# PartA.net
KiCad netlist of a schematic drawn in Altium Designer
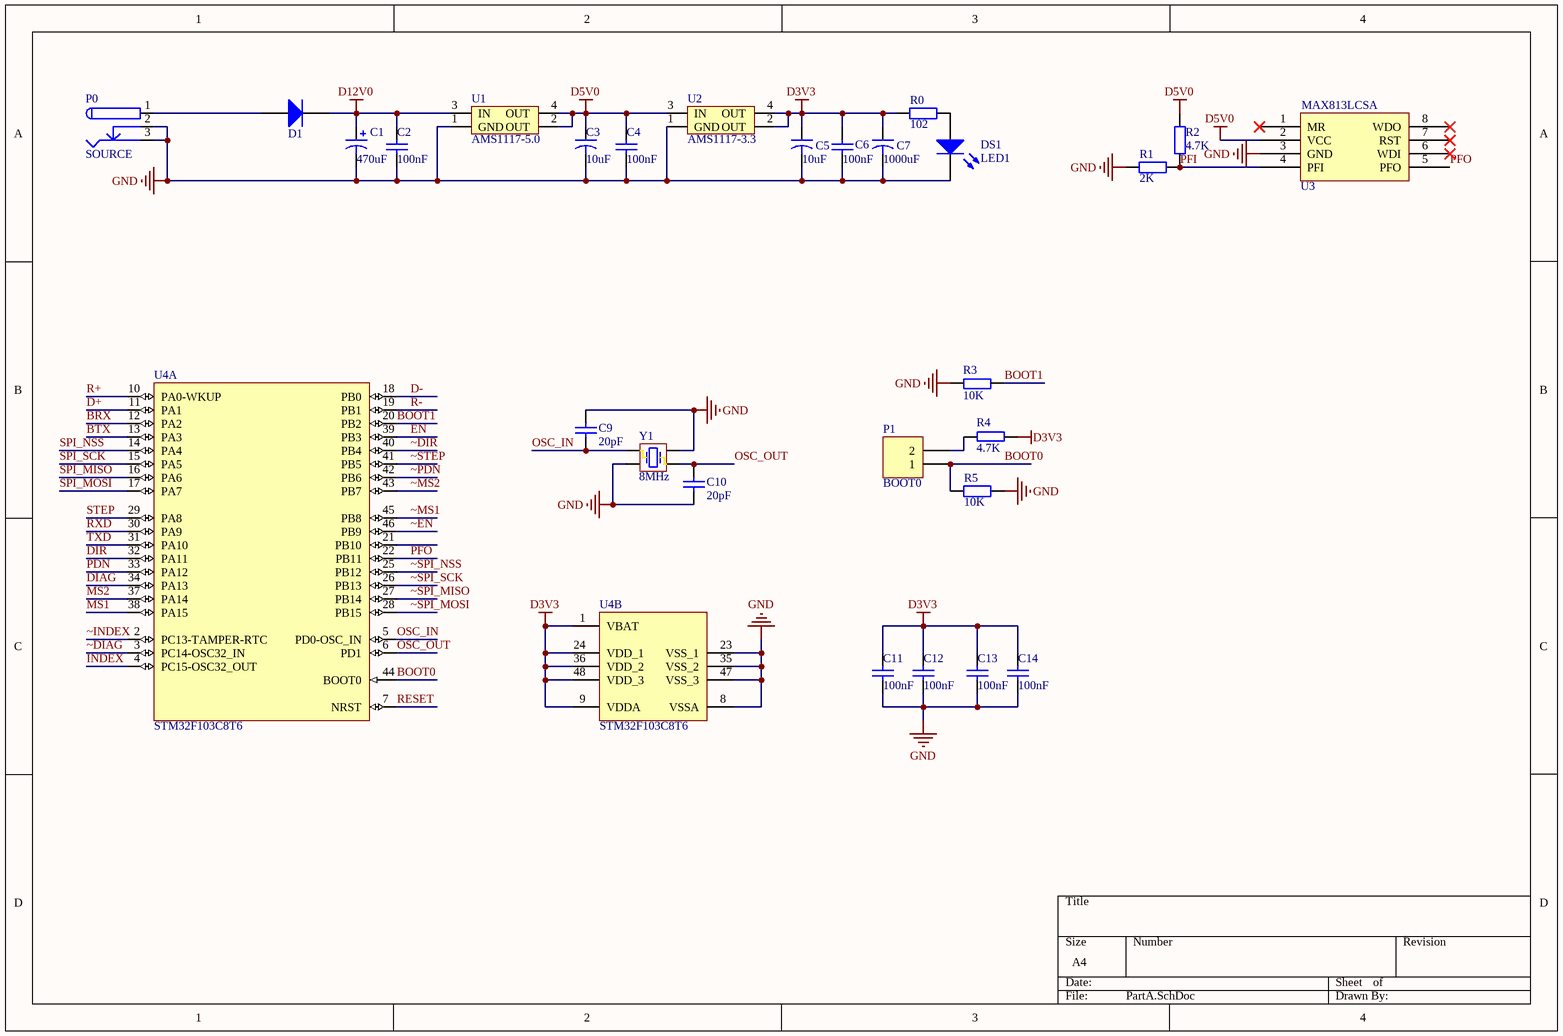
[diagram p0: PartA.SchDoc]

(export (version "E")
  (design (tool "Eeschema 10.0.6"))
  (components
    (comp (ref "C1")
      (value "470uF")
      (footprint "CAP8")
      (description "470UF      16V      CD10X10D5")
      (libsource (lib "平台原理图symbol图库V1.0") (part "C470UF016S"))
    )
    (comp (ref "C2")
      (value "100nF")
      (footprint "0603C")
      (description "Capacitor")
      (fields (field (name "PUBLISHER") "Altium Limited"))
      (libsource (lib "Crazy_PCB") (part "Cap"))
    )
    (comp (ref "C3")
      (value "10uF")
      (footprint "3216")
      (fields (field (name "VAULE") "10uF"))
      (libsource (lib "Crazy_PCB") (part "CAP2"))
    )
    (comp (ref "C4")
      (value "100nF")
      (footprint "0603C")
      (description "Capacitor")
      (fields (field (name "PUBLISHER") "Altium Limited"))
      (libsource (lib "Crazy_PCB") (part "Cap"))
    )
    (comp (ref "C5")
      (value "10uF")
      (footprint "3216")
      (fields (field (name "VAULE") "10uF"))
      (libsource (lib "Crazy_PCB") (part "CAP2"))
    )
    (comp (ref "C6")
      (value "100nF")
      (footprint "0603C")
      (description "Capacitor")
      (fields (field (name "PUBLISHER") "Altium Limited"))
      (libsource (lib "Crazy_PCB") (part "Cap"))
    )
    (comp (ref "C7")
      (value "1000uF")
      (footprint "CAP8")
      (fields (field (name "VAULE") "1000uF"))
      (libsource (lib "Crazy_PCB") (part "CAP2"))
    )
    (comp (ref "C9")
      (value "20pF")
      (footprint "0603C")
      (description "Capacitor")
      (fields (field (name "PUBLISHER") "Altium Limited"))
      (libsource (lib "JL_SCH") (part "Cap"))
    )
    (comp (ref "C10")
      (value "20pF")
      (footprint "0603C")
      (description "Capacitor")
      (fields (field (name "PUBLISHER") "Altium Limited"))
      (libsource (lib "JL_SCH") (part "Cap"))
    )
    (comp (ref "C11")
      (value "100nF")
      (footprint "0603C")
      (description "Capacitor")
      (fields (field (name "PUBLISHER") "Altium Limited"))
      (libsource (lib "Crazy_PCB") (part "Cap"))
    )
    (comp (ref "C12")
      (value "100nF")
      (footprint "0603C")
      (description "Capacitor")
      (fields (field (name "PUBLISHER") "Altium Limited"))
      (libsource (lib "Crazy_PCB") (part "Cap"))
    )
    (comp (ref "C13")
      (value "100nF")
      (footprint "0603C")
      (description "Capacitor")
      (fields (field (name "PUBLISHER") "Altium Limited"))
      (libsource (lib "Crazy_PCB") (part "Cap"))
    )
    (comp (ref "C14")
      (value "100nF")
      (footprint "0603C")
      (description "Capacitor")
      (fields (field (name "PUBLISHER") "Altium Limited"))
      (libsource (lib "Crazy_PCB") (part "Cap"))
    )
    (comp (ref "D1")
      (value "M7")
      (footprint "DO-214AC")
      (description "High Conductance Fast Diode")
      (fields (field (name "PUBLISHER") "Altium Limited"))
      (libsource (lib "Crazy_PCB") (part "Diode"))
    )
    (comp (ref "DS1")
      (value "LED1")
      (footprint "0805D")
      (description "Typical RED, GREEN, YELLOW, AMBER GaAs LED")
      (fields (field (name "PUBLISHER") "Altium Limited"))
      (libsource (lib "MiniSTM32 V3.0封装库") (part "LED2"))
    )
    (comp (ref "P0")
      (value "SOURCE")
      (footprint "DC_5.5MM")
      (fields (field (name "PUBLISHER") "Altium Limited"))
      (libsource (lib "Crazy_PCB") (part "SOURCE"))
    )
    (comp (ref "P1")
      (value "BOOT0")
      (footprint "HDR1X2")
      (description "Header, 2-Pin")
      (fields (field (name "PUBLISHER") "Altium Limited"))
      (libsource (lib "Miscellaneous Connectors") (part "MHDR1X2"))
    )
    (comp (ref "R0")
      (value "102")
      (footprint "0603R")
      (description "Resistor")
      (fields (field (name "PUBLISHER") "Altium Limited"))
      (libsource (lib "Crazy_PCB") (part "RES"))
    )
    (comp (ref "R1")
      (value "2K")
      (footprint "0603R")
      (description "Resistor")
      (fields (field (name "PUBLISHER") "Altium Limited"))
      (libsource (lib "") (part "RES_1"))
    )
    (comp (ref "R2")
      (value "4.7K")
      (footprint "0603R")
      (description "Resistor")
      (fields (field (name "PUBLISHER") "Altium Limited"))
      (libsource (lib "") (part "RES_2"))
    )
    (comp (ref "R3") (value "10K") (footprint "0603R") (libsource (lib "WarShip V3 STM32103封装库") (part "R")))
    (comp (ref "R4") (value "4.7K") (footprint "0603R") (libsource (lib "WarShip V3 STM32103封装库") (part "R")))
    (comp (ref "R5")
      (value "10K")
      (footprint "0603R")
      (description "Resistor")
      (fields (field (name "PUBLISHER") "Altium Limited"))
      (libsource (lib "") (part "RES_1"))
    )
    (comp (ref "U1")
      (value "AMS1117-5.0")
      (footprint "SOT223")
      (libsource (lib "MiniSTM32 V3.0封装库") (part "AMS1117"))
    )
    (comp (ref "U2")
      (value "AMS1117-3.3")
      (footprint "SOT223")
      (libsource (lib "MiniSTM32 V3.0封装库") (part "AMS1117"))
    )
    (comp (ref "U3") (value "MAX813LCSA") (footprint "SOP-8") (libsource (lib "DX") (part "MAX813L")))
    (comp (ref "U4")
      (value "STM32F103C8T6")
      (footprint "LQFP48_N")
      (libsource (lib "STMicroelectronics STM32 F1") (part "STM32F103C8T6"))
    )
    (comp (ref "Y1")
      (value "8MHz")
      (footprint "X3225")
      (description "Crystal Oscillator")
      (fields (field (name "PUBLISHER") "Altium Limited"))
      (libsource (lib "JL_SCH") (part "XTAL_1"))
    )
  )
  (nets
    (net (code "1") (name "/BOOT0") (class "Default")
      (node (ref "P1") (pin "1") (pinfunction "1_1") (pintype "passive"))
      (node (ref "R5") (pin "1") (pinfunction "1_1") (pintype "passive"))
      (node (ref "U4") (pin "44") (pinfunction "BOOT0_44") (pintype "input"))
    )
    (net (code "2") (name "/BOOT1") (class "Default")
      (node (ref "R3") (pin "2") (pintype "passive"))
      (node (ref "U4") (pin "20") (pinfunction "PB2_20") (pintype "bidirectional"))
    )
    (net (code "3") (name "/BRX") (class "Default")
      (node (ref "U4") (pin "12") (pinfunction "PA2_12") (pintype "bidirectional"))
    )
    (net (code "4") (name "/BTX") (class "Default")
      (node (ref "U4") (pin "13") (pinfunction "PA3_13") (pintype "bidirectional"))
    )
    (net (code "5") (name "/D+") (class "Default")
      (node (ref "U4") (pin "11") (pinfunction "PA1_11") (pintype "bidirectional"))
    )
    (net (code "6") (name "/D-") (class "Default")
      (node (ref "U4") (pin "18") (pinfunction "PB0_18") (pintype "bidirectional"))
    )
    (net (code "7") (name "/DIAG") (class "Default")
      (node (ref "U4") (pin "34") (pinfunction "PA13_34") (pintype "bidirectional"))
    )
    (net (code "8") (name "/DIR") (class "Default")
      (node (ref "U4") (pin "32") (pinfunction "PA11_32") (pintype "bidirectional"))
    )
    (net (code "9") (name "/EN") (class "Default")
      (node (ref "U4") (pin "39") (pinfunction "PB3_39") (pintype "bidirectional"))
    )
    (net (code "10") (name "/INDEX") (class "Default")
      (node (ref "U4") (pin "4") (pinfunction "PC15-OSC32_OUT_4") (pintype "bidirectional"))
    )
    (net (code "11") (name "/MS1") (class "Default")
      (node (ref "U4") (pin "38") (pinfunction "PA15_38") (pintype "bidirectional"))
    )
    (net (code "12") (name "/MS2") (class "Default")
      (node (ref "U4") (pin "37") (pinfunction "PA14_37") (pintype "bidirectional"))
    )
    (net (code "13") (name "/OSC_IN") (class "Default")
      (node (ref "C9") (pin "1") (pinfunction "1_1") (pintype "passive"))
      (node (ref "U4") (pin "5") (pinfunction "PD0-OSC_IN_5") (pintype "bidirectional"))
      (node (ref "Y1") (pin "1") (pinfunction "OSC1_1") (pintype "passive"))
    )
    (net (code "14") (name "/OSC_OUT") (class "Default")
      (node (ref "C10") (pin "1") (pinfunction "1_1") (pintype "passive"))
      (node (ref "U4") (pin "6") (pinfunction "PD1_6") (pintype "bidirectional"))
      (node (ref "Y1") (pin "3") (pinfunction "OSC2_3") (pintype "passive"))
    )
    (net (code "15") (name "/PDN") (class "Default")
      (node (ref "U4") (pin "33") (pinfunction "PA12_33") (pintype "bidirectional"))
    )
    (net (code "16") (name "/PFI") (class "Default")
      (node (ref "R1") (pin "2") (pinfunction "2_2") (pintype "passive"))
      (node (ref "R2") (pin "1") (pinfunction "1_1") (pintype "passive"))
      (node (ref "U3") (pin "4") (pinfunction "PFI_4") (pintype "passive"))
    )
    (net (code "17") (name "/PFO") (class "Default")
      (node (ref "U3") (pin "5") (pinfunction "PFO_5") (pintype "passive"))
      (node (ref "U4") (pin "22") (pinfunction "PB11_22") (pintype "bidirectional"))
    )
    (net (code "18") (name "/R+") (class "Default")
      (node (ref "U4") (pin "10") (pinfunction "PA0-WKUP_10") (pintype "bidirectional"))
    )
    (net (code "19") (name "/R-") (class "Default")
      (node (ref "U4") (pin "19") (pinfunction "PB1_19") (pintype "bidirectional"))
    )
    (net (code "20") (name "/RESET") (class "Default")
      (node (ref "U4") (pin "7") (pinfunction "NRST_7") (pintype "bidirectional"))
    )
    (net (code "21") (name "/RXD") (class "Default")
      (node (ref "U4") (pin "30") (pinfunction "PA9_30") (pintype "bidirectional"))
    )
    (net (code "22") (name "/SPI_MISO") (class "Default")
      (node (ref "U4") (pin "16") (pinfunction "PA6_16") (pintype "bidirectional"))
    )
    (net (code "23") (name "/SPI_MOSI") (class "Default")
      (node (ref "U4") (pin "17") (pinfunction "PA7_17") (pintype "bidirectional"))
    )
    (net (code "24") (name "/SPI_NSS") (class "Default")
      (node (ref "U4") (pin "14") (pinfunction "PA4_14") (pintype "bidirectional"))
    )
    (net (code "25") (name "/SPI_SCK") (class "Default")
      (node (ref "U4") (pin "15") (pinfunction "PA5_15") (pintype "bidirectional"))
    )
    (net (code "26") (name "/STEP") (class "Default")
      (node (ref "U4") (pin "29") (pinfunction "PA8_29") (pintype "bidirectional"))
    )
    (net (code "27") (name "/TXD") (class "Default")
      (node (ref "U4") (pin "31") (pinfunction "PA10_31") (pintype "bidirectional"))
    )
    (net (code "28") (name "/~DIAG") (class "Default")
      (node (ref "U4") (pin "3") (pinfunction "PC14-OSC32_IN_3") (pintype "bidirectional"))
    )
    (net (code "29") (name "/~DIR") (class "Default")
      (node (ref "U4") (pin "40") (pinfunction "PB4_40") (pintype "bidirectional"))
    )
    (net (code "30") (name "/~EN") (class "Default")
      (node (ref "U4") (pin "46") (pinfunction "PB9_46") (pintype "bidirectional"))
    )
    (net (code "31") (name "/~INDEX") (class "Default")
      (node (ref "U4") (pin "2") (pinfunction "PC13-TAMPER-RTC_2") (pintype "bidirectional"))
    )
    (net (code "32") (name "/~MS1") (class "Default")
      (node (ref "U4") (pin "45") (pinfunction "PB8_45") (pintype "bidirectional"))
    )
    (net (code "33") (name "/~MS2") (class "Default")
      (node (ref "U4") (pin "43") (pinfunction "PB7_43") (pintype "bidirectional"))
    )
    (net (code "34") (name "/~PDN") (class "Default")
      (node (ref "U4") (pin "42") (pinfunction "PB6_42") (pintype "bidirectional"))
    )
    (net (code "35") (name "/~SPI_MISO") (class "Default")
      (node (ref "U4") (pin "27") (pinfunction "PB14_27") (pintype "bidirectional"))
    )
    (net (code "36") (name "/~SPI_MOSI") (class "Default")
      (node (ref "U4") (pin "28") (pinfunction "PB15_28") (pintype "bidirectional"))
    )
    (net (code "37") (name "/~SPI_NSS") (class "Default")
      (node (ref "U4") (pin "25") (pinfunction "PB12_25") (pintype "bidirectional"))
    )
    (net (code "38") (name "/~SPI_SCK") (class "Default")
      (node (ref "U4") (pin "26") (pinfunction "PB13_26") (pintype "bidirectional"))
    )
    (net (code "39") (name "/~STEP") (class "Default")
      (node (ref "U4") (pin "41") (pinfunction "PB5_41") (pintype "bidirectional"))
    )
    (net (code "40") (name "D3V3") (class "Default")
      (node (ref "C11") (pin "2") (pinfunction "2_2") (pintype "passive"))
      (node (ref "C12") (pin "2") (pinfunction "2_2") (pintype "passive"))
      (node (ref "C13") (pin "2") (pinfunction "2_2") (pintype "passive"))
      (node (ref "C14") (pin "2") (pinfunction "2_2") (pintype "passive"))
      (node (ref "C5") (pin "1") (pinfunction "1_1") (pintype "passive"))
      (node (ref "C6") (pin "2") (pinfunction "2_2") (pintype "passive"))
      (node (ref "C7") (pin "1") (pinfunction "1_1") (pintype "passive"))
      (node (ref "R0") (pin "2") (pinfunction "2_2") (pintype "passive"))
      (node (ref "R4") (pin "1") (pintype "passive"))
      (node (ref "U2") (pin "2") (pinfunction "OUT_2") (pintype "passive"))
      (node (ref "U2") (pin "4") (pinfunction "OUT_4") (pintype "passive"))
      (node (ref "U4") (pin "1") (pinfunction "VBAT_1") (pintype "power_in"))
      (node (ref "U4") (pin "24") (pinfunction "VDD_1_24") (pintype "power_in"))
      (node (ref "U4") (pin "36") (pinfunction "VDD_2_36") (pintype "power_in"))
      (node (ref "U4") (pin "48") (pinfunction "VDD_3_48") (pintype "power_in"))
      (node (ref "U4") (pin "9") (pinfunction "VDDA_9") (pintype "power_in"))
    )
    (net (code "41") (name "D5V0") (class "Default")
      (node (ref "C3") (pin "1") (pinfunction "1_1") (pintype "passive"))
      (node (ref "C4") (pin "2") (pinfunction "2_2") (pintype "passive"))
      (node (ref "R2") (pin "2") (pinfunction "2_2") (pintype "passive"))
      (node (ref "U1") (pin "2") (pinfunction "OUT_2") (pintype "passive"))
      (node (ref "U1") (pin "4") (pinfunction "OUT_4") (pintype "passive"))
      (node (ref "U2") (pin "3") (pinfunction "IN_3") (pintype "passive"))
      (node (ref "U3") (pin "2") (pinfunction "VCC_2") (pintype "passive"))
    )
    (net (code "42") (name "D12V0") (class "Default")
      (node (ref "C1") (pin "1") (pinfunction "1_1") (pintype "passive"))
      (node (ref "C2") (pin "2") (pinfunction "2_2") (pintype "passive"))
      (node (ref "D1") (pin "2") (pinfunction "K_2") (pintype "passive"))
      (node (ref "U1") (pin "3") (pinfunction "IN_3") (pintype "passive"))
    )
    (net (code "43") (name "GND") (class "Default")
      (node (ref "C1") (pin "2") (pinfunction "2_2") (pintype "passive"))
      (node (ref "C10") (pin "2") (pinfunction "2_2") (pintype "passive"))
      (node (ref "C11") (pin "1") (pinfunction "1_1") (pintype "passive"))
      (node (ref "C12") (pin "1") (pinfunction "1_1") (pintype "passive"))
      (node (ref "C13") (pin "1") (pinfunction "1_1") (pintype "passive"))
      (node (ref "C14") (pin "1") (pinfunction "1_1") (pintype "passive"))
      (node (ref "C2") (pin "1") (pinfunction "1_1") (pintype "passive"))
      (node (ref "C3") (pin "2") (pinfunction "2_2") (pintype "passive"))
      (node (ref "C4") (pin "1") (pinfunction "1_1") (pintype "passive"))
      (node (ref "C5") (pin "2") (pinfunction "2_2") (pintype "passive"))
      (node (ref "C6") (pin "1") (pinfunction "1_1") (pintype "passive"))
      (node (ref "C7") (pin "2") (pinfunction "2_2") (pintype "passive"))
      (node (ref "C9") (pin "2") (pinfunction "2_2") (pintype "passive"))
      (node (ref "DS1") (pin "2") (pinfunction "K_2") (pintype "passive"))
      (node (ref "P0") (pin "2") (pinfunction "2_2") (pintype "power_in"))
      (node (ref "P0") (pin "3") (pinfunction "3_3") (pintype "power_in"))
      (node (ref "R1") (pin "1") (pinfunction "1_1") (pintype "passive"))
      (node (ref "R3") (pin "1") (pintype "passive"))
      (node (ref "R5") (pin "2") (pinfunction "2_2") (pintype "passive"))
      (node (ref "U1") (pin "1") (pinfunction "GND_1") (pintype "passive"))
      (node (ref "U2") (pin "1") (pinfunction "GND_1") (pintype "passive"))
      (node (ref "U3") (pin "3") (pinfunction "GND_3") (pintype "passive"))
      (node (ref "U4") (pin "23") (pinfunction "VSS_1_23") (pintype "power_in"))
      (node (ref "U4") (pin "35") (pinfunction "VSS_2_35") (pintype "power_in"))
      (node (ref "U4") (pin "47") (pinfunction "VSS_3_47") (pintype "power_in"))
      (node (ref "U4") (pin "8") (pinfunction "VSSA_8") (pintype "power_in"))
      (node (ref "Y1") (pin "2") (pinfunction "NA_2") (pintype "passive"))
      (node (ref "Y1") (pin "4") (pinfunction "NA_4") (pintype "passive"))
    )
    (net (code "44") (name "Net-(D1-A)") (class "Default")
      (node (ref "D1") (pin "1") (pinfunction "A_1") (pintype "passive"))
      (node (ref "P0") (pin "1") (pinfunction "1_1") (pintype "power_in"))
    )
    (net (code "45") (name "Net-(DS1-A)") (class "Default")
      (node (ref "DS1") (pin "1") (pinfunction "A_1") (pintype "passive"))
      (node (ref "R0") (pin "1") (pinfunction "1_1") (pintype "passive"))
    )
    (net (code "46") (name "Net-(P1-Pad2)") (class "Default")
      (node (ref "P1") (pin "2") (pinfunction "2_2") (pintype "passive"))
      (node (ref "R4") (pin "2") (pintype "passive"))
    )
    (net (code "47") (name "unconnected-(U3-MR-Pad1)") (class "Default")
      (node (ref "U3") (pin "1") (pinfunction "MR_1") (pintype "passive+no_connect"))
    )
    (net (code "48") (name "unconnected-(U3-RST-Pad7)") (class "Default")
      (node (ref "U3") (pin "7") (pinfunction "RST_7") (pintype "passive+no_connect"))
    )
    (net (code "49") (name "unconnected-(U3-WDI-Pad6)") (class "Default")
      (node (ref "U3") (pin "6") (pinfunction "WDI_6") (pintype "passive+no_connect"))
    )
    (net (code "50") (name "unconnected-(U3-WDO-Pad8)") (class "Default")
      (node (ref "U3") (pin "8") (pinfunction "WDO_8") (pintype "passive+no_connect"))
    )
    (net (code "51") (name "unconnected-(U4A-PB10-Pad21)") (class "Default")
      (node (ref "U4") (pin "21") (pinfunction "PB10_21") (pintype "bidirectional"))
    )
  )
)
